# Amp2.net
KiCad netlist of a schematic drawn in EasyEDA
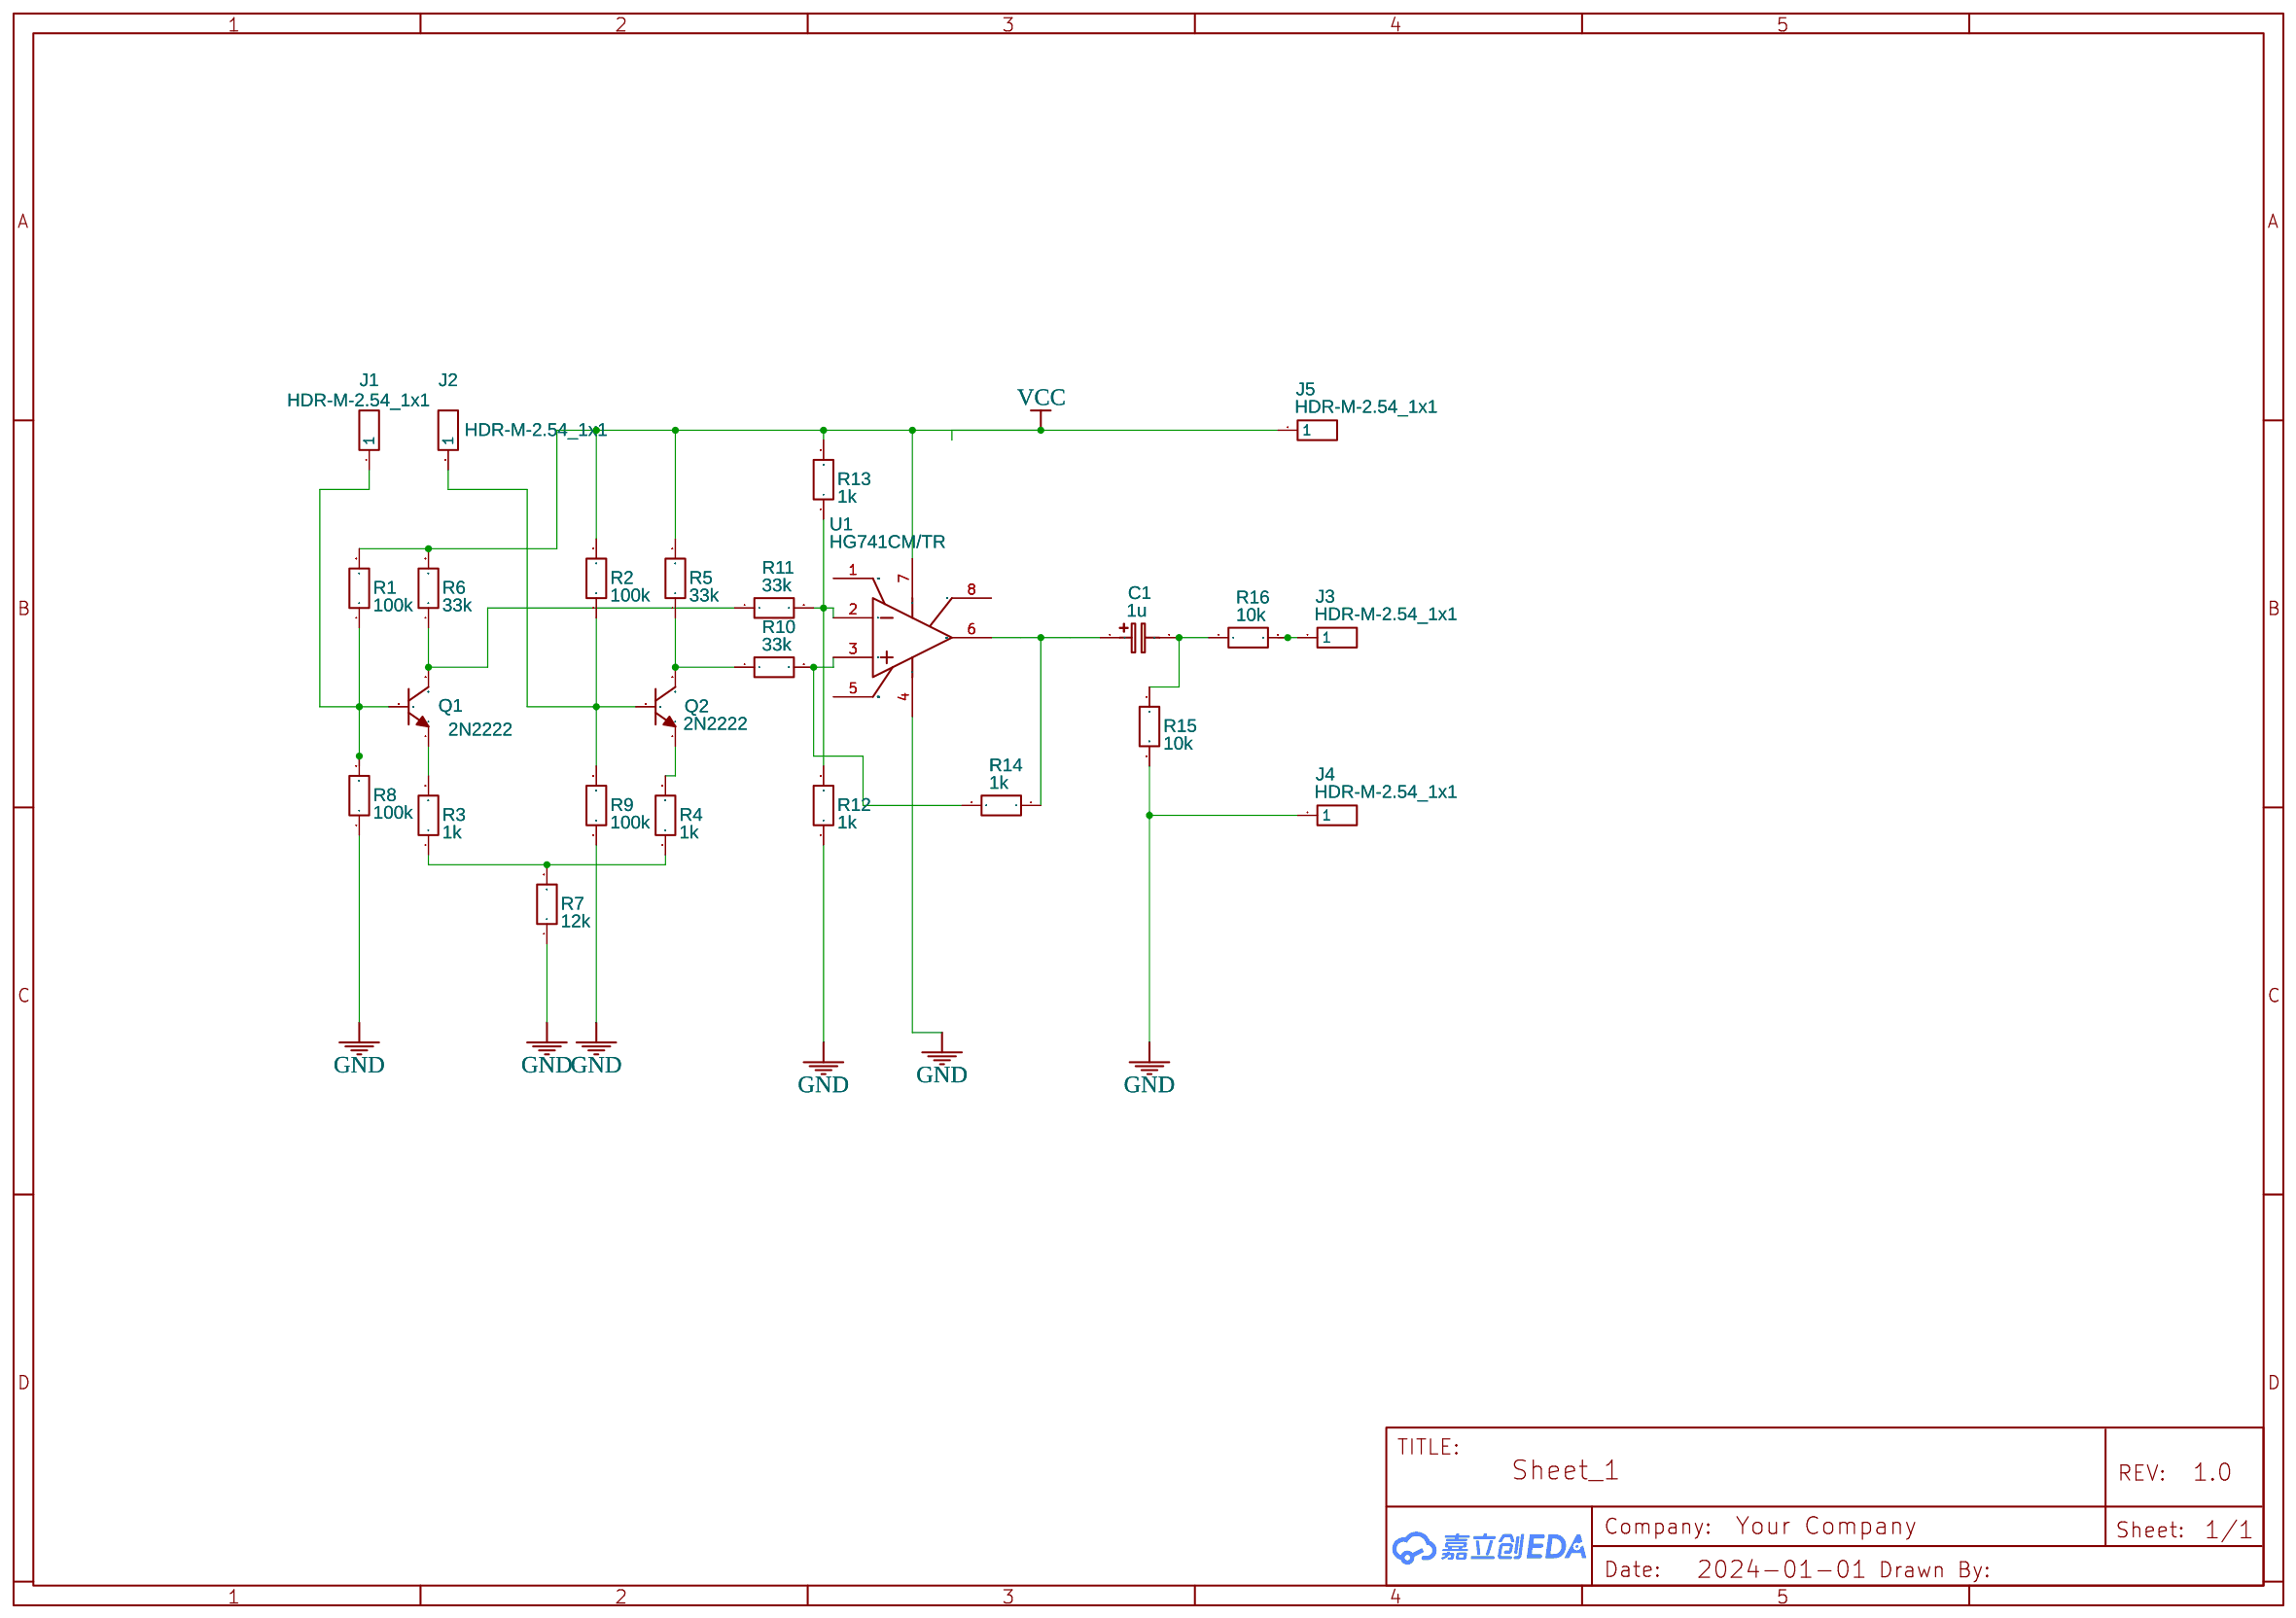
[diagram p0: schematic sheet]

(export (version "E")
  (design (tool "Eeschema 10.0.6"))
  (components
    (comp (ref "C1") (value "1u") (libsource (lib "") (part "C_Tan_SMD_A_EU")))
    (comp (ref "J1")
      (value "HDR-M-2.54_1x1")
      (fields (field (name "BOM_Supplier Part") "C81276"))
      (libsource (lib "") (part "HDR-M-2.54_1x1"))
    )
    (comp (ref "J2")
      (value "HDR-M-2.54_1x1")
      (fields (field (name "BOM_Supplier Part") "C81276"))
      (libsource (lib "") (part "HDR-M-2.54_1x1"))
    )
    (comp (ref "J3")
      (value "HDR-M-2.54_1x1")
      (fields (field (name "BOM_Supplier Part") "C81276"))
      (libsource (lib "") (part "HDR-M-2.54_1x1_1"))
    )
    (comp (ref "J4")
      (value "HDR-M-2.54_1x1")
      (fields (field (name "BOM_Supplier Part") "C81276"))
      (libsource (lib "") (part "HDR-M-2.54_1x1_1"))
    )
    (comp (ref "J5")
      (value "HDR-M-2.54_1x1")
      (fields (field (name "BOM_Supplier Part") "C81276"))
      (libsource (lib "") (part "HDR-M-2.54_1x1_1"))
    )
    (comp (ref "Q1")
      (value "2N2222")
      (fields
        (field (name "BOM_Manufacturer Part") "2n3904S-RTK/PS")
        (field (name "BOM_Supplier Part") "C18536")
      )
      (libsource (lib "") (part "2N3904(SOT-23)"))
    )
    (comp (ref "Q2")
      (value "2N2222")
      (fields
        (field (name "BOM_Manufacturer Part") "2n3904S-RTK/PS")
        (field (name "BOM_Supplier Part") "C18536")
      )
      (libsource (lib "") (part "2N3904(SOT-23)"))
    )
    (comp (ref "R1") (value "100k") (libsource (lib "") (part "R_0603_EU_1")))
    (comp (ref "R2") (value "100k") (libsource (lib "") (part "R_0603_EU_1")))
    (comp (ref "R3") (value "1k") (libsource (lib "") (part "R_0603_EU_1")))
    (comp (ref "R4") (value "1k") (libsource (lib "") (part "R_0603_EU_1")))
    (comp (ref "R5") (value "33k") (libsource (lib "") (part "R_0603_EU_1")))
    (comp (ref "R6") (value "33k") (libsource (lib "") (part "R_0603_EU_1")))
    (comp (ref "R7") (value "12k") (libsource (lib "") (part "R_0603_EU_1")))
    (comp (ref "R8") (value "100k") (libsource (lib "") (part "R_0603_EU_1")))
    (comp (ref "R9") (value "100k") (libsource (lib "") (part "R_0603_EU_1")))
    (comp (ref "R10") (value "33k") (libsource (lib "") (part "R_0603_EU_2")))
    (comp (ref "R11") (value "33k") (libsource (lib "") (part "R_0603_EU_2")))
    (comp (ref "R12") (value "1k") (libsource (lib "") (part "R_0603_EU_1")))
    (comp (ref "R13") (value "1k") (libsource (lib "") (part "R_0603_EU_1")))
    (comp (ref "R14") (value "1k") (libsource (lib "") (part "R_0603_EU")))
    (comp (ref "R15") (value "10k") (libsource (lib "") (part "R_0603_EU_3")))
    (comp (ref "R16") (value "10k") (libsource (lib "") (part "R_0603_EU_2")))
    (comp (ref "U1")
      (value "HG741CM/TR")
      (fields (field (name "Manufacturer") "HGSEMI(华冠)"))
      (libsource (lib "") (part "HG741CM/TR"))
    )
  )
  (nets
    (net (code "1") (name "GND") (class "Default")
      (node (ref "J4") (pin "1") (pinfunction "1_1") (pintype "input"))
      (node (ref "R12") (pin "1") (pinfunction "1_1") (pintype "unspecified"))
      (node (ref "R15") (pin "2") (pinfunction "2_2") (pintype "unspecified"))
      (node (ref "R7") (pin "1") (pinfunction "1_1") (pintype "unspecified"))
      (node (ref "R8") (pin "1") (pinfunction "1_1") (pintype "unspecified"))
      (node (ref "R9") (pin "1") (pinfunction "1_1") (pintype "unspecified"))
      (node (ref "U1") (pin "4") (pinfunction "V-_4") (pintype "passive"))
    )
    (net (code "2") (name "Net-(C1-Pad2)") (class "Default")
      (node (ref "C1") (pin "2") (pinfunction "2_2") (pintype "unspecified"))
      (node (ref "R15") (pin "1") (pinfunction "1_1") (pintype "unspecified"))
      (node (ref "R16") (pin "1") (pinfunction "1_1") (pintype "unspecified"))
    )
    (net (code "3") (name "Net-(J3-Pad1)") (class "Default")
      (node (ref "J3") (pin "1") (pinfunction "1_1") (pintype "input"))
      (node (ref "R16") (pin "2") (pinfunction "2_2") (pintype "unspecified"))
    )
    (net (code "4") (name "Net-(Q1-B)") (class "Default")
      (node (ref "J1") (pin "1") (pinfunction "1_1") (pintype "input"))
      (node (ref "Q1") (pin "2") (pinfunction "B_2") (pintype "input"))
      (node (ref "R1") (pin "1") (pinfunction "1_1") (pintype "unspecified"))
      (node (ref "R8") (pin "2") (pinfunction "2_2") (pintype "unspecified"))
    )
    (net (code "5") (name "Net-(Q1-C)") (class "Default")
      (node (ref "Q1") (pin "3") (pinfunction "C_3") (pintype "input"))
      (node (ref "R11") (pin "1") (pinfunction "1_1") (pintype "unspecified"))
      (node (ref "R6") (pin "1") (pinfunction "1_1") (pintype "unspecified"))
    )
    (net (code "6") (name "Net-(Q1-E)") (class "Default")
      (node (ref "Q1") (pin "1") (pinfunction "E_1") (pintype "input"))
      (node (ref "R3") (pin "2") (pinfunction "2_2") (pintype "unspecified"))
    )
    (net (code "7") (name "Net-(Q2-B)") (class "Default")
      (node (ref "J2") (pin "1") (pinfunction "1_1") (pintype "input"))
      (node (ref "Q2") (pin "2") (pinfunction "B_2") (pintype "input"))
      (node (ref "R2") (pin "1") (pinfunction "1_1") (pintype "unspecified"))
      (node (ref "R9") (pin "2") (pinfunction "2_2") (pintype "unspecified"))
    )
    (net (code "8") (name "Net-(Q2-C)") (class "Default")
      (node (ref "Q2") (pin "3") (pinfunction "C_3") (pintype "input"))
      (node (ref "R10") (pin "1") (pinfunction "1_1") (pintype "unspecified"))
      (node (ref "R5") (pin "1") (pinfunction "1_1") (pintype "unspecified"))
    )
    (net (code "9") (name "Net-(Q2-E)") (class "Default")
      (node (ref "Q2") (pin "1") (pinfunction "E_1") (pintype "input"))
      (node (ref "R4") (pin "2") (pinfunction "2_2") (pintype "unspecified"))
    )
    (net (code "10") (name "Net-(R3-Pad1)") (class "Default")
      (node (ref "R3") (pin "1") (pinfunction "1_1") (pintype "unspecified"))
      (node (ref "R4") (pin "1") (pinfunction "1_1") (pintype "unspecified"))
      (node (ref "R7") (pin "2") (pinfunction "2_2") (pintype "unspecified"))
    )
    (net (code "11") (name "Net-(U1-+IN)") (class "Default")
      (node (ref "R10") (pin "2") (pinfunction "2_2") (pintype "unspecified"))
      (node (ref "R14") (pin "2") (pinfunction "2_2") (pintype "unspecified"))
      (node (ref "U1") (pin "3") (pinfunction "+IN_3") (pintype "unspecified"))
    )
    (net (code "12") (name "Net-(U1--IN)") (class "Default")
      (node (ref "R11") (pin "2") (pinfunction "2_2") (pintype "unspecified"))
      (node (ref "R12") (pin "2") (pinfunction "2_2") (pintype "unspecified"))
      (node (ref "R13") (pin "1") (pinfunction "1_1") (pintype "unspecified"))
      (node (ref "U1") (pin "2") (pinfunction "-IN_2") (pintype "unspecified"))
    )
    (net (code "13") (name "Net-(U1-OUTPUT)") (class "Default")
      (node (ref "C1") (pin "1") (pinfunction "1_1") (pintype "unspecified"))
      (node (ref "R14") (pin "1") (pinfunction "1_1") (pintype "unspecified"))
      (node (ref "U1") (pin "6") (pinfunction "OUTPUT_6") (pintype "unspecified"))
    )
    (net (code "14") (name "VCC") (class "Default")
      (node (ref "J5") (pin "1") (pinfunction "1_1") (pintype "input"))
      (node (ref "R1") (pin "2") (pinfunction "2_2") (pintype "unspecified"))
      (node (ref "R13") (pin "2") (pinfunction "2_2") (pintype "unspecified"))
      (node (ref "R2") (pin "2") (pinfunction "2_2") (pintype "unspecified"))
      (node (ref "R5") (pin "2") (pinfunction "2_2") (pintype "unspecified"))
      (node (ref "R6") (pin "2") (pinfunction "2_2") (pintype "unspecified"))
      (node (ref "U1") (pin "7") (pinfunction "V+_7") (pintype "passive"))
    )
    (net (code "15") (name "unconnected-(U1-NC-Pad8)") (class "Default")
      (node (ref "U1") (pin "8") (pinfunction "NC_8") (pintype "unspecified"))
    )
    (net (code "16") (name "unconnected-(U1-OFFSET_NULL-Pad1)") (class "Default")
      (node (ref "U1") (pin "1") (pinfunction "OFFSET_NULL_1") (pintype "unspecified"))
    )
    (net (code "17") (name "unconnected-(U1-OFFSET_NULL-Pad5)") (class "Default")
      (node (ref "U1") (pin "5") (pinfunction "OFFSET_NULL_5") (pintype "unspecified"))
    )
  )
)
